# IA_Asserv_Shield.net
KiCad netlist of a schematic drawn in EAGLE
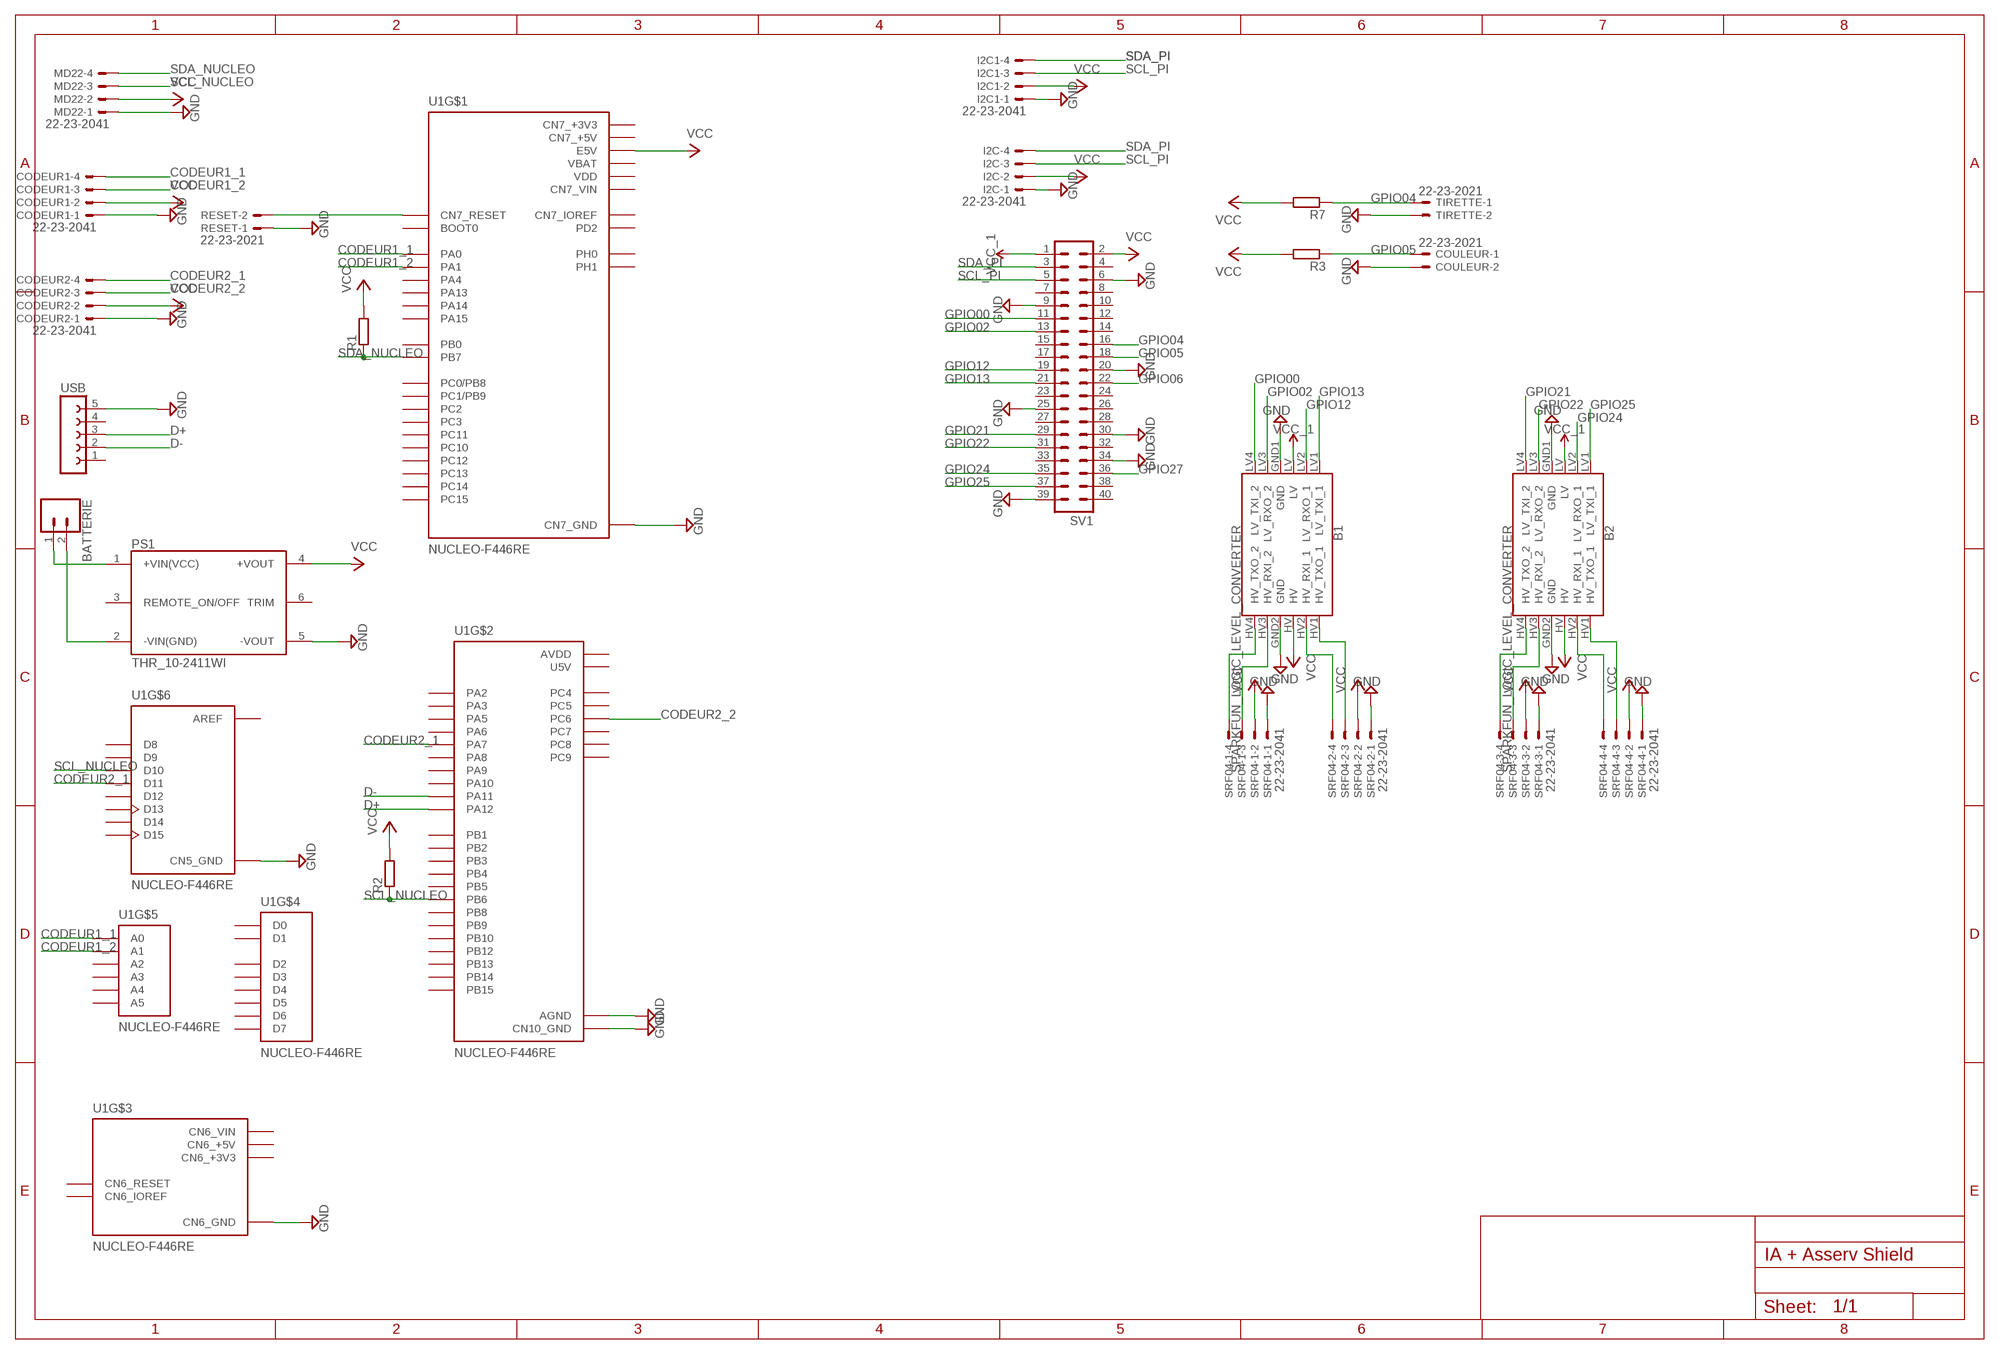
[diagram p0: schematic, sheet 1]

(export (version "E")
  (design (tool "Eeschema 10.0.6"))
  (components
    (comp (ref "B1")
      (value "SPARKFUN_LOGIC_LEVEL_CONVERTER")
      (footprint "eagle-import:SPARKFUN_LOGIC_LEVEL_CONVERTER")
      (libsource (lib "eagle-import") (part "SPARKFUN_LOGIC_LEVEL_CONVERTER"))
    )
    (comp (ref "B2")
      (value "SPARKFUN_LOGIC_LEVEL_CONVERTER")
      (footprint "eagle-import:SPARKFUN_LOGIC_LEVEL_CONVERTER")
      (libsource (lib "eagle-import") (part "SPARKFUN_LOGIC_LEVEL_CONVERTER"))
    )
    (comp (ref "BATTERIE")
      (value "CONN_02POLAR")
      (footprint "eagle-import:MOLEX-1X2")
      (libsource (lib "eagle-import") (part "CONN_02POLAR"))
    )
    (comp (ref "CODEUR1")
      (value "22-23-2041")
      (footprint "eagle-import:22-23-2041")
      (fields (field (name "MF") "MOLEX"))
      (libsource (lib "eagle-import") (part "22-23-2041"))
    )
    (comp (ref "CODEUR2")
      (value "22-23-2041")
      (footprint "eagle-import:22-23-2041")
      (fields (field (name "MF") "MOLEX"))
      (libsource (lib "eagle-import") (part "22-23-2041"))
    )
    (comp (ref "COULEUR")
      (value "22-23-2021")
      (footprint "eagle-import:22-23-2021")
      (fields (field (name "MF") "MOLEX"))
      (libsource (lib "eagle-import") (part "22-23-2021"))
    )
    (comp (ref "I2C")
      (value "22-23-2041")
      (footprint "eagle-import:22-23-2041")
      (fields (field (name "MF") "MOLEX"))
      (libsource (lib "eagle-import") (part "22-23-2041"))
    )
    (comp (ref "I2C1")
      (value "22-23-2041")
      (footprint "eagle-import:22-23-2041")
      (fields (field (name "MF") "MOLEX"))
      (libsource (lib "eagle-import") (part "22-23-2041"))
    )
    (comp (ref "MD22")
      (value "22-23-2041")
      (footprint "eagle-import:22-23-2041")
      (fields (field (name "MF") "MOLEX"))
      (libsource (lib "eagle-import") (part "22-23-2041"))
    )
    (comp (ref "PS1")
      (value "THR_10-2411WI")
      (footprint "eagle-import:CONV_THR_10-2411WI")
      (fields (field (name "MF") "Traco Power") (field (name "MP") "THR 10-2411WI"))
      (libsource (lib "eagle-import") (part "THR_10-2411WI"))
    )
    (comp (ref "R1")
      (value "R-EU_0204/7")
      (footprint "eagle-import:0204_7")
      (libsource (lib "eagle-import") (part "R-EU_0204/7"))
    )
    (comp (ref "R2")
      (value "R-EU_0204/7")
      (footprint "eagle-import:0204_7")
      (libsource (lib "eagle-import") (part "R-EU_0204/7"))
    )
    (comp (ref "R3")
      (value "R-EU_0204/7")
      (footprint "eagle-import:0204_7")
      (libsource (lib "eagle-import") (part "R-EU_0204/7"))
    )
    (comp (ref "R7")
      (value "R-EU_0204/7")
      (footprint "eagle-import:0204_7")
      (libsource (lib "eagle-import") (part "R-EU_0204/7"))
    )
    (comp (ref "RESET")
      (value "22-23-2021")
      (footprint "eagle-import:22-23-2021")
      (fields (field (name "MF") "MOLEX"))
      (libsource (lib "eagle-import") (part "22-23-2021"))
    )
    (comp (ref "SRF04-1")
      (value "22-23-2041")
      (footprint "eagle-import:22-23-2041")
      (fields (field (name "MF") "MOLEX"))
      (libsource (lib "eagle-import") (part "22-23-2041"))
    )
    (comp (ref "SRF04-2")
      (value "22-23-2041")
      (footprint "eagle-import:22-23-2041")
      (fields (field (name "MF") "MOLEX"))
      (libsource (lib "eagle-import") (part "22-23-2041"))
    )
    (comp (ref "SRF04-3")
      (value "22-23-2041")
      (footprint "eagle-import:22-23-2041")
      (fields (field (name "MF") "MOLEX"))
      (libsource (lib "eagle-import") (part "22-23-2041"))
    )
    (comp (ref "SRF04-4")
      (value "22-23-2041")
      (footprint "eagle-import:22-23-2041")
      (fields (field (name "MF") "MOLEX"))
      (libsource (lib "eagle-import") (part "22-23-2041"))
    )
    (comp (ref "SV1")
      (value "MA20-2")
      (footprint "eagle-import:MA20-2")
      (libsource (lib "eagle-import") (part "MA20-2"))
    )
    (comp (ref "TIRETTE")
      (value "22-23-2021")
      (footprint "eagle-import:22-23-2021")
      (fields (field (name "MF") "MOLEX"))
      (libsource (lib "eagle-import") (part "22-23-2021"))
    )
    (comp (ref "U1")
      (value "NUCLEO-F446RE")
      (footprint "eagle-import:MODULE_NUCLEO-F446RE")
      (fields
        (field (name "MF") "STMicroelectronics")
        (field (name "MF_1") "STMICROELECTRONICS")
        (field (name "SPICEPREFIX") "X")
        (field (name "MPN") "NUCLEO-F446RE")
        (field (name "OC_FARNELL") "2491978")
      )
      (libsource (lib "eagle-import") (part "NUCLEO-F446RE"))
    )
    (comp (ref "USB")
      (value "FE05-1")
      (footprint "eagle-import:FE05-1")
      (libsource (lib "eagle-import") (part "FE05-1"))
    )
  )
  (nets
    (net (code "1") (name "/AREF") (class "Default")
      (node (ref "U1") (pin "CN5_8") (pinfunction "AREF_CN5_8") (pintype "power_in"))
    )
    (net (code "2") (name "/AVDD") (class "Default")
      (node (ref "U1") (pin "CN10_7") (pinfunction "AVDD_CN10_7") (pintype "power_in"))
    )
    (net (code "3") (name "/CN6_+3V3") (class "Default")
      (node (ref "U1") (pin "CN6_4") (pinfunction "CN6_+3V3_CN6_4") (pintype "power_in"))
    )
    (net (code "4") (name "/CN6_+5V") (class "Default")
      (node (ref "U1") (pin "CN6_5") (pinfunction "CN6_+5V_CN6_5") (pintype "power_in"))
    )
    (net (code "5") (name "/CN6_VIN") (class "Default")
      (node (ref "U1") (pin "CN6_8") (pinfunction "CN6_VIN_CN6_8") (pintype "power_in"))
    )
    (net (code "6") (name "/CN7_+3V3") (class "Default")
      (node (ref "U1") (pin "CN7_16") (pinfunction "CN7_+3V3_CN7_16") (pintype "power_in"))
    )
    (net (code "7") (name "/CN7_+5V") (class "Default")
      (node (ref "U1") (pin "CN7_18") (pinfunction "CN7_+5V_CN7_18") (pintype "power_in"))
    )
    (net (code "8") (name "/CN7_VIN") (class "Default")
      (node (ref "U1") (pin "CN7_24") (pinfunction "CN7_VIN_CN7_24") (pintype "power_in"))
    )
    (net (code "9") (name "/CODEUR1_1") (class "Default")
      (node (ref "CODEUR1") (pin "4") (pinfunction "S_4") (pintype "passive"))
      (node (ref "U1") (pin "CN7_28") (pinfunction "PA0_CN7_28") (pintype "bidirectional"))
      (node (ref "U1") (pin "CN8_1") (pinfunction "A0_CN8_1") (pintype "input"))
    )
    (net (code "10") (name "/CODEUR1_2") (class "Default")
      (node (ref "CODEUR1") (pin "3") (pinfunction "S_3") (pintype "passive"))
      (node (ref "U1") (pin "CN7_30") (pinfunction "PA1_CN7_30") (pintype "bidirectional"))
      (node (ref "U1") (pin "CN8_2") (pinfunction "A1_CN8_2") (pintype "input"))
    )
    (net (code "11") (name "/CODEUR2_1") (class "Default")
      (node (ref "CODEUR2") (pin "4") (pinfunction "S_4") (pintype "passive"))
      (node (ref "U1") (pin "CN10_15") (pinfunction "PA7_CN10_15") (pintype "bidirectional"))
      (node (ref "U1") (pin "CN5_4") (pinfunction "D11_CN5_4") (pintype "bidirectional"))
    )
    (net (code "12") (name "/CODEUR2_2") (class "Default")
      (node (ref "CODEUR2") (pin "3") (pinfunction "S_3") (pintype "passive"))
      (node (ref "U1") (pin "CN10_4") (pinfunction "PC6_CN10_4") (pintype "bidirectional"))
    )
    (net (code "13") (name "/D+") (class "Default")
      (node (ref "U1") (pin "CN10_12") (pinfunction "PA12_CN10_12") (pintype "bidirectional"))
      (node (ref "USB") (pin "3") (pinfunction "3_3") (pintype "passive"))
    )
    (net (code "14") (name "/D-") (class "Default")
      (node (ref "U1") (pin "CN10_14") (pinfunction "PA11_CN10_14") (pintype "bidirectional"))
      (node (ref "USB") (pin "2") (pinfunction "2_2") (pintype "passive"))
    )
    (net (code "15") (name "/GPIO00") (class "Default")
      (node (ref "B1") (pin "LV4") (pinfunction "LV_TXI_2_LV4") (pintype "bidirectional"))
      (node (ref "SV1") (pin "11") (pinfunction "11_11") (pintype "passive"))
    )
    (net (code "16") (name "/GPIO02") (class "Default")
      (node (ref "B1") (pin "LV3") (pinfunction "LV_RXO_2_LV3") (pintype "bidirectional"))
      (node (ref "SV1") (pin "13") (pinfunction "13_13") (pintype "passive"))
    )
    (net (code "17") (name "/GPIO04") (class "Default")
      (node (ref "R7") (pin "1") (pinfunction "1_1") (pintype "passive"))
      (node (ref "SV1") (pin "16") (pinfunction "16_16") (pintype "passive"))
      (node (ref "TIRETTE") (pin "1") (pinfunction "S_1") (pintype "passive"))
    )
    (net (code "18") (name "/GPIO05") (class "Default")
      (node (ref "COULEUR") (pin "1") (pinfunction "S_1") (pintype "passive"))
      (node (ref "R3") (pin "1") (pinfunction "1_1") (pintype "passive"))
      (node (ref "SV1") (pin "18") (pinfunction "18_18") (pintype "passive"))
    )
    (net (code "19") (name "/GPIO06") (class "Default")
      (node (ref "SV1") (pin "22") (pinfunction "22_22") (pintype "passive"))
    )
    (net (code "20") (name "/GPIO12") (class "Default")
      (node (ref "B1") (pin "LV2") (pinfunction "LV_RXO_1_LV2") (pintype "bidirectional"))
      (node (ref "SV1") (pin "19") (pinfunction "19_19") (pintype "passive"))
    )
    (net (code "21") (name "/GPIO13") (class "Default")
      (node (ref "B1") (pin "LV1") (pinfunction "LV_TXI_1_LV1") (pintype "bidirectional"))
      (node (ref "SV1") (pin "21") (pinfunction "21_21") (pintype "passive"))
    )
    (net (code "22") (name "/GPIO21") (class "Default")
      (node (ref "B2") (pin "LV4") (pinfunction "LV_TXI_2_LV4") (pintype "bidirectional"))
      (node (ref "SV1") (pin "29") (pinfunction "29_29") (pintype "passive"))
    )
    (net (code "23") (name "/GPIO22") (class "Default")
      (node (ref "B2") (pin "LV3") (pinfunction "LV_RXO_2_LV3") (pintype "bidirectional"))
      (node (ref "SV1") (pin "31") (pinfunction "31_31") (pintype "passive"))
    )
    (net (code "24") (name "/GPIO24") (class "Default")
      (node (ref "B2") (pin "LV2") (pinfunction "LV_RXO_1_LV2") (pintype "bidirectional"))
      (node (ref "SV1") (pin "35") (pinfunction "35_35") (pintype "passive"))
    )
    (net (code "25") (name "/GPIO25") (class "Default")
      (node (ref "B2") (pin "LV1") (pinfunction "LV_TXI_1_LV1") (pintype "bidirectional"))
      (node (ref "SV1") (pin "37") (pinfunction "37_37") (pintype "passive"))
    )
    (net (code "26") (name "/GPIO27") (class "Default")
      (node (ref "SV1") (pin "36") (pinfunction "36_36") (pintype "passive"))
    )
    (net (code "27") (name "/SCL_NUCLEO") (class "Default")
      (node (ref "MD22") (pin "3") (pinfunction "S_3") (pintype "passive"))
      (node (ref "R2") (pin "1") (pinfunction "1_1") (pintype "passive"))
      (node (ref "U1") (pin "CN10_17") (pinfunction "PB6_CN10_17") (pintype "bidirectional"))
      (node (ref "U1") (pin "CN5_3") (pinfunction "D10_CN5_3") (pintype "bidirectional"))
    )
    (net (code "28") (name "/SCL_PI") (class "Default")
      (node (ref "I2C") (pin "3") (pinfunction "S_3") (pintype "passive"))
      (node (ref "I2C1") (pin "3") (pinfunction "S_3") (pintype "passive"))
      (node (ref "SV1") (pin "5") (pinfunction "5_5") (pintype "passive"))
    )
    (net (code "29") (name "/SDA_NUCLEO") (class "Default")
      (node (ref "MD22") (pin "4") (pinfunction "S_4") (pintype "passive"))
      (node (ref "R1") (pin "1") (pinfunction "1_1") (pintype "passive"))
      (node (ref "U1") (pin "CN7_21") (pinfunction "PB7_CN7_21") (pintype "bidirectional"))
    )
    (net (code "30") (name "/SDA_PI") (class "Default")
      (node (ref "I2C") (pin "4") (pinfunction "S_4") (pintype "passive"))
      (node (ref "I2C1") (pin "4") (pinfunction "S_4") (pintype "passive"))
      (node (ref "SV1") (pin "3") (pinfunction "3_3") (pintype "passive"))
    )
    (net (code "31") (name "/U5V") (class "Default")
      (node (ref "U1") (pin "CN10_8") (pinfunction "U5V_CN10_8") (pintype "power_in"))
    )
    (net (code "32") (name "/VBAT") (class "Default")
      (node (ref "U1") (pin "CN7_33") (pinfunction "VBAT_CN7_33") (pintype "power_in"))
    )
    (net (code "33") (name "/VDD") (class "Default")
      (node (ref "U1") (pin "CN7_5") (pinfunction "VDD_CN7_5") (pintype "power_in"))
    )
    (net (code "34") (name "GND") (class "Default")
      (node (ref "B1") (pin "GND1") (pinfunction "GND_GND1") (pintype "power_in"))
      (node (ref "B1") (pin "GND2") (pinfunction "GND_GND2") (pintype "power_in"))
      (node (ref "B2") (pin "GND1") (pinfunction "GND_GND1") (pintype "power_in"))
      (node (ref "B2") (pin "GND2") (pinfunction "GND_GND2") (pintype "power_in"))
      (node (ref "CODEUR1") (pin "1") (pinfunction "S_1") (pintype "passive"))
      (node (ref "CODEUR2") (pin "1") (pinfunction "S_1") (pintype "passive"))
      (node (ref "COULEUR") (pin "2") (pinfunction "S_2") (pintype "passive"))
      (node (ref "I2C") (pin "1") (pinfunction "S_1") (pintype "passive"))
      (node (ref "I2C1") (pin "1") (pinfunction "S_1") (pintype "passive"))
      (node (ref "MD22") (pin "1") (pinfunction "S_1") (pintype "passive"))
      (node (ref "PS1") (pin "5") (pinfunction "-VOUT_5") (pintype "output"))
      (node (ref "RESET") (pin "1") (pinfunction "S_1") (pintype "passive"))
      (node (ref "SRF04-1") (pin "1") (pinfunction "S_1") (pintype "passive"))
      (node (ref "SRF04-2") (pin "1") (pinfunction "S_1") (pintype "passive"))
      (node (ref "SRF04-3") (pin "1") (pinfunction "S_1") (pintype "passive"))
      (node (ref "SRF04-4") (pin "1") (pinfunction "S_1") (pintype "passive"))
      (node (ref "SV1") (pin "20") (pinfunction "20_20") (pintype "passive"))
      (node (ref "SV1") (pin "25") (pinfunction "25_25") (pintype "passive"))
      (node (ref "SV1") (pin "30") (pinfunction "30_30") (pintype "passive"))
      (node (ref "SV1") (pin "34") (pinfunction "34_34") (pintype "passive"))
      (node (ref "SV1") (pin "39") (pinfunction "39_39") (pintype "passive"))
      (node (ref "SV1") (pin "6") (pinfunction "6_6") (pintype "passive"))
      (node (ref "SV1") (pin "9") (pinfunction "9_9") (pintype "passive"))
      (node (ref "TIRETTE") (pin "2") (pinfunction "S_2") (pintype "passive"))
      (node (ref "U1") (pin "CN10_20") (pinfunction "CN10_GND_CN10_20") (pintype "power_in"))
      (node (ref "U1") (pin "CN10_32") (pinfunction "AGND_CN10_32") (pintype "power_in"))
      (node (ref "U1") (pin "CN10_9") (pinfunction "CN10_GND_CN10_9") (pintype "power_in"))
      (node (ref "U1") (pin "CN5_7") (pinfunction "CN5_GND_CN5_7") (pintype "power_in"))
      (node (ref "U1") (pin "CN6_6") (pinfunction "CN6_GND_CN6_6") (pintype "power_in"))
      (node (ref "U1") (pin "CN6_7") (pinfunction "CN6_GND_CN6_7") (pintype "power_in"))
      (node (ref "U1") (pin "CN7_19") (pinfunction "CN7_GND_CN7_19") (pintype "power_in"))
      (node (ref "U1") (pin "CN7_20") (pinfunction "CN7_GND_CN7_20") (pintype "power_in"))
      (node (ref "U1") (pin "CN7_22") (pinfunction "CN7_GND_CN7_22") (pintype "power_in"))
      (node (ref "U1") (pin "CN7_8") (pinfunction "CN7_GND_CN7_8") (pintype "power_in"))
      (node (ref "USB") (pin "5") (pinfunction "5_5") (pintype "passive"))
    )
    (net (code "35") (name "Net-(B1-HV_RXI_1)") (class "Default")
      (node (ref "B1") (pin "HV2") (pinfunction "HV_RXI_1_HV2") (pintype "bidirectional"))
      (node (ref "SRF04-2") (pin "4") (pinfunction "S_4") (pintype "passive"))
    )
    (net (code "36") (name "Net-(B1-HV_RXI_2)") (class "Default")
      (node (ref "B1") (pin "HV3") (pinfunction "HV_RXI_2_HV3") (pintype "bidirectional"))
      (node (ref "SRF04-1") (pin "3") (pinfunction "S_3") (pintype "passive"))
    )
    (net (code "37") (name "Net-(B1-HV_TXO_1)") (class "Default")
      (node (ref "B1") (pin "HV1") (pinfunction "HV_TXO_1_HV1") (pintype "bidirectional"))
      (node (ref "SRF04-2") (pin "3") (pinfunction "S_3") (pintype "passive"))
    )
    (net (code "38") (name "Net-(B1-HV_TXO_2)") (class "Default")
      (node (ref "B1") (pin "HV4") (pinfunction "HV_TXO_2_HV4") (pintype "bidirectional"))
      (node (ref "SRF04-1") (pin "4") (pinfunction "S_4") (pintype "passive"))
    )
    (net (code "39") (name "Net-(B2-HV_RXI_1)") (class "Default")
      (node (ref "B2") (pin "HV2") (pinfunction "HV_RXI_1_HV2") (pintype "bidirectional"))
      (node (ref "SRF04-4") (pin "4") (pinfunction "S_4") (pintype "passive"))
    )
    (net (code "40") (name "Net-(B2-HV_RXI_2)") (class "Default")
      (node (ref "B2") (pin "HV3") (pinfunction "HV_RXI_2_HV3") (pintype "bidirectional"))
      (node (ref "SRF04-3") (pin "3") (pinfunction "S_3") (pintype "passive"))
    )
    (net (code "41") (name "Net-(B2-HV_TXO_1)") (class "Default")
      (node (ref "B2") (pin "HV1") (pinfunction "HV_TXO_1_HV1") (pintype "bidirectional"))
      (node (ref "SRF04-4") (pin "3") (pinfunction "S_3") (pintype "passive"))
    )
    (net (code "42") (name "Net-(B2-HV_TXO_2)") (class "Default")
      (node (ref "B2") (pin "HV4") (pinfunction "HV_TXO_2_HV4") (pintype "bidirectional"))
      (node (ref "SRF04-3") (pin "4") (pinfunction "S_4") (pintype "passive"))
    )
    (net (code "43") (name "Net-(PS1-+VIN(VCC))") (class "Default")
      (node (ref "BATTERIE") (pin "1") (pinfunction "1_1") (pintype "passive"))
      (node (ref "PS1") (pin "1") (pinfunction "+VIN(VCC)_1") (pintype "input"))
    )
    (net (code "44") (name "Net-(PS1--VIN(GND))") (class "Default")
      (node (ref "BATTERIE") (pin "2") (pinfunction "2_2") (pintype "passive"))
      (node (ref "PS1") (pin "2") (pinfunction "-VIN(GND)_2") (pintype "input"))
    )
    (net (code "45") (name "Net-(RESETB-S)") (class "Default")
      (node (ref "RESET") (pin "2") (pinfunction "S_2") (pintype "passive"))
      (node (ref "U1") (pin "CN7_14") (pinfunction "CN7_RESET_CN7_14") (pintype "bidirectional"))
    )
    (net (code "46") (name "VCC") (class "Default")
      (node (ref "B1") (pin "HV") (pinfunction "HV_HV") (pintype "power_in"))
      (node (ref "B2") (pin "HV") (pinfunction "HV_HV") (pintype "power_in"))
      (node (ref "CODEUR1") (pin "2") (pinfunction "S_2") (pintype "passive"))
      (node (ref "CODEUR2") (pin "2") (pinfunction "S_2") (pintype "passive"))
      (node (ref "I2C") (pin "2") (pinfunction "S_2") (pintype "passive"))
      (node (ref "I2C1") (pin "2") (pinfunction "S_2") (pintype "passive"))
      (node (ref "MD22") (pin "2") (pinfunction "S_2") (pintype "passive"))
      (node (ref "PS1") (pin "4") (pinfunction "+VOUT_4") (pintype "output"))
      (node (ref "R1") (pin "2") (pinfunction "2_2") (pintype "passive"))
      (node (ref "R2") (pin "2") (pinfunction "2_2") (pintype "passive"))
      (node (ref "R3") (pin "2") (pinfunction "2_2") (pintype "passive"))
      (node (ref "R7") (pin "2") (pinfunction "2_2") (pintype "passive"))
      (node (ref "SRF04-1") (pin "2") (pinfunction "S_2") (pintype "passive"))
      (node (ref "SRF04-2") (pin "2") (pinfunction "S_2") (pintype "passive"))
      (node (ref "SRF04-3") (pin "2") (pinfunction "S_2") (pintype "passive"))
      (node (ref "SRF04-4") (pin "2") (pinfunction "S_2") (pintype "passive"))
      (node (ref "SV1") (pin "2") (pinfunction "2_2") (pintype "passive"))
      (node (ref "U1") (pin "CN7_6") (pinfunction "E5V_CN7_6") (pintype "power_in"))
    )
    (net (code "47") (name "VCC_1") (class "Default")
      (node (ref "B1") (pin "LV") (pinfunction "LV_LV") (pintype "power_in"))
      (node (ref "B2") (pin "LV") (pinfunction "LV_LV") (pintype "power_in"))
      (node (ref "SV1") (pin "1") (pinfunction "1_1") (pintype "passive"))
    )
    (net (code "48") (name "unconnected-(PS1-REMOTE_ON{slash}OFF-Pad3)") (class "Default")
      (node (ref "PS1") (pin "3") (pinfunction "REMOTE_ON/OFF_3") (pintype "input"))
    )
    (net (code "49") (name "unconnected-(PS1-TRIM-Pad6)") (class "Default")
      (node (ref "PS1") (pin "6") (pinfunction "TRIM_6") (pintype "passive"))
    )
    (net (code "50") (name "unconnected-(SV1-Pad4)") (class "Default")
      (node (ref "SV1") (pin "4") (pinfunction "4_4") (pintype "passive"))
    )
    (net (code "51") (name "unconnected-(SV1-Pad7)") (class "Default")
      (node (ref "SV1") (pin "7") (pinfunction "7_7") (pintype "passive"))
    )
    (net (code "52") (name "unconnected-(SV1-Pad8)") (class "Default")
      (node (ref "SV1") (pin "8") (pinfunction "8_8") (pintype "passive"))
    )
    (net (code "53") (name "unconnected-(SV1-Pad10)") (class "Default")
      (node (ref "SV1") (pin "10") (pinfunction "10_10") (pintype "passive"))
    )
    (net (code "54") (name "unconnected-(SV1-Pad12)") (class "Default")
      (node (ref "SV1") (pin "12") (pinfunction "12_12") (pintype "passive"))
    )
    (net (code "55") (name "unconnected-(SV1-Pad14)") (class "Default")
      (node (ref "SV1") (pin "14") (pinfunction "14_14") (pintype "passive"))
    )
    (net (code "56") (name "unconnected-(SV1-Pad15)") (class "Default")
      (node (ref "SV1") (pin "15") (pinfunction "15_15") (pintype "passive"))
    )
    (net (code "57") (name "unconnected-(SV1-Pad17)") (class "Default")
      (node (ref "SV1") (pin "17") (pinfunction "17_17") (pintype "passive"))
    )
    (net (code "58") (name "unconnected-(SV1-Pad23)") (class "Default")
      (node (ref "SV1") (pin "23") (pinfunction "23_23") (pintype "passive"))
    )
    (net (code "59") (name "unconnected-(SV1-Pad24)") (class "Default")
      (node (ref "SV1") (pin "24") (pinfunction "24_24") (pintype "passive"))
    )
    (net (code "60") (name "unconnected-(SV1-Pad26)") (class "Default")
      (node (ref "SV1") (pin "26") (pinfunction "26_26") (pintype "passive"))
    )
    (net (code "61") (name "unconnected-(SV1-Pad27)") (class "Default")
      (node (ref "SV1") (pin "27") (pinfunction "27_27") (pintype "passive"))
    )
    (net (code "62") (name "unconnected-(SV1-Pad28)") (class "Default")
      (node (ref "SV1") (pin "28") (pinfunction "28_28") (pintype "passive"))
    )
    (net (code "63") (name "unconnected-(SV1-Pad32)") (class "Default")
      (node (ref "SV1") (pin "32") (pinfunction "32_32") (pintype "passive"))
    )
    (net (code "64") (name "unconnected-(SV1-Pad33)") (class "Default")
      (node (ref "SV1") (pin "33") (pinfunction "33_33") (pintype "passive"))
    )
    (net (code "65") (name "unconnected-(SV1-Pad38)") (class "Default")
      (node (ref "SV1") (pin "38") (pinfunction "38_38") (pintype "passive"))
    )
    (net (code "66") (name "unconnected-(SV1-Pad40)") (class "Default")
      (node (ref "SV1") (pin "40") (pinfunction "40_40") (pintype "passive"))
    )
    (net (code "67") (name "unconnected-(U1A-BOOT0-PadCN7_7)") (class "Default")
      (node (ref "U1") (pin "CN7_7") (pinfunction "BOOT0_CN7_7") (pintype "bidirectional"))
    )
    (net (code "68") (name "unconnected-(U1A-CN7_IOREF-PadCN7_12)") (class "Default")
      (node (ref "U1") (pin "CN7_12") (pinfunction "CN7_IOREF_CN7_12") (pintype "bidirectional"))
    )
    (net (code "69") (name "unconnected-(U1A-PA4-PadCN7_32)") (class "Default")
      (node (ref "U1") (pin "CN7_32") (pinfunction "PA4_CN7_32") (pintype "bidirectional"))
    )
    (net (code "70") (name "unconnected-(U1A-PA13-PadCN7_13)") (class "Default")
      (node (ref "U1") (pin "CN7_13") (pinfunction "PA13_CN7_13") (pintype "bidirectional"))
    )
    (net (code "71") (name "unconnected-(U1A-PA14-PadCN7_15)") (class "Default")
      (node (ref "U1") (pin "CN7_15") (pinfunction "PA14_CN7_15") (pintype "bidirectional"))
    )
    (net (code "72") (name "unconnected-(U1A-PA15-PadCN7_17)") (class "Default")
      (node (ref "U1") (pin "CN7_17") (pinfunction "PA15_CN7_17") (pintype "bidirectional"))
    )
    (net (code "73") (name "unconnected-(U1A-PB0-PadCN7_34)") (class "Default")
      (node (ref "U1") (pin "CN7_34") (pinfunction "PB0_CN7_34") (pintype "bidirectional"))
    )
    (net (code "74") (name "unconnected-(U1A-PC0{slash}PB8-PadCN7_38)") (class "Default")
      (node (ref "U1") (pin "CN7_38") (pinfunction "PC0/PB8_CN7_38") (pintype "bidirectional"))
    )
    (net (code "75") (name "unconnected-(U1A-PC1{slash}PB9-PadCN7_36)") (class "Default")
      (node (ref "U1") (pin "CN7_36") (pinfunction "PC1/PB9_CN7_36") (pintype "bidirectional"))
    )
    (net (code "76") (name "unconnected-(U1A-PC2-PadCN7_35)") (class "Default")
      (node (ref "U1") (pin "CN7_35") (pinfunction "PC2_CN7_35") (pintype "bidirectional"))
    )
    (net (code "77") (name "unconnected-(U1A-PC3-PadCN7_37)") (class "Default")
      (node (ref "U1") (pin "CN7_37") (pinfunction "PC3_CN7_37") (pintype "bidirectional"))
    )
    (net (code "78") (name "unconnected-(U1A-PC10-PadCN7_1)") (class "Default")
      (node (ref "U1") (pin "CN7_1") (pinfunction "PC10_CN7_1") (pintype "bidirectional"))
    )
    (net (code "79") (name "unconnected-(U1A-PC11-PadCN7_2)") (class "Default")
      (node (ref "U1") (pin "CN7_2") (pinfunction "PC11_CN7_2") (pintype "bidirectional"))
    )
    (net (code "80") (name "unconnected-(U1A-PC12-PadCN7_3)") (class "Default")
      (node (ref "U1") (pin "CN7_3") (pinfunction "PC12_CN7_3") (pintype "bidirectional"))
    )
    (net (code "81") (name "unconnected-(U1A-PC13-PadCN7_23)") (class "Default")
      (node (ref "U1") (pin "CN7_23") (pinfunction "PC13_CN7_23") (pintype "bidirectional"))
    )
    (net (code "82") (name "unconnected-(U1A-PC14-PadCN7_25)") (class "Default")
      (node (ref "U1") (pin "CN7_25") (pinfunction "PC14_CN7_25") (pintype "bidirectional"))
    )
    (net (code "83") (name "unconnected-(U1A-PC15-PadCN7_27)") (class "Default")
      (node (ref "U1") (pin "CN7_27") (pinfunction "PC15_CN7_27") (pintype "bidirectional"))
    )
    (net (code "84") (name "unconnected-(U1A-PD2-PadCN7_4)") (class "Default")
      (node (ref "U1") (pin "CN7_4") (pinfunction "PD2_CN7_4") (pintype "bidirectional"))
    )
    (net (code "85") (name "unconnected-(U1A-PH0-PadCN7_29)") (class "Default")
      (node (ref "U1") (pin "CN7_29") (pinfunction "PH0_CN7_29") (pintype "bidirectional"))
    )
    (net (code "86") (name "unconnected-(U1A-PH1-PadCN7_31)") (class "Default")
      (node (ref "U1") (pin "CN7_31") (pinfunction "PH1_CN7_31") (pintype "bidirectional"))
    )
    (net (code "87") (name "unconnected-(U1B-PA2-PadCN10_35)") (class "Default")
      (node (ref "U1") (pin "CN10_35") (pinfunction "PA2_CN10_35") (pintype "bidirectional"))
    )
    (net (code "88") (name "unconnected-(U1B-PA3-PadCN10_37)") (class "Default")
      (node (ref "U1") (pin "CN10_37") (pinfunction "PA3_CN10_37") (pintype "bidirectional"))
    )
    (net (code "89") (name "unconnected-(U1B-PA5-PadCN10_11)") (class "Default")
      (node (ref "U1") (pin "CN10_11") (pinfunction "PA5_CN10_11") (pintype "bidirectional"))
    )
    (net (code "90") (name "unconnected-(U1B-PA6-PadCN10_13)") (class "Default")
      (node (ref "U1") (pin "CN10_13") (pinfunction "PA6_CN10_13") (pintype "bidirectional"))
    )
    (net (code "91") (name "unconnected-(U1B-PA8-PadCN10_23)") (class "Default")
      (node (ref "U1") (pin "CN10_23") (pinfunction "PA8_CN10_23") (pintype "bidirectional"))
    )
    (net (code "92") (name "unconnected-(U1B-PA9-PadCN10_21)") (class "Default")
      (node (ref "U1") (pin "CN10_21") (pinfunction "PA9_CN10_21") (pintype "bidirectional"))
    )
    (net (code "93") (name "unconnected-(U1B-PA10-PadCN10_33)") (class "Default")
      (node (ref "U1") (pin "CN10_33") (pinfunction "PA10_CN10_33") (pintype "bidirectional"))
    )
    (net (code "94") (name "unconnected-(U1B-PB1-PadCN10_24)") (class "Default")
      (node (ref "U1") (pin "CN10_24") (pinfunction "PB1_CN10_24") (pintype "bidirectional"))
    )
    (net (code "95") (name "unconnected-(U1B-PB2-PadCN10_22)") (class "Default")
      (node (ref "U1") (pin "CN10_22") (pinfunction "PB2_CN10_22") (pintype "bidirectional"))
    )
    (net (code "96") (name "unconnected-(U1B-PB3-PadCN10_31)") (class "Default")
      (node (ref "U1") (pin "CN10_31") (pinfunction "PB3_CN10_31") (pintype "bidirectional"))
    )
    (net (code "97") (name "unconnected-(U1B-PB4-PadCN10_27)") (class "Default")
      (node (ref "U1") (pin "CN10_27") (pinfunction "PB4_CN10_27") (pintype "bidirectional"))
    )
    (net (code "98") (name "unconnected-(U1B-PB5-PadCN10_29)") (class "Default")
      (node (ref "U1") (pin "CN10_29") (pinfunction "PB5_CN10_29") (pintype "bidirectional"))
    )
    (net (code "99") (name "unconnected-(U1B-PB8-PadCN10_3)") (class "Default")
      (node (ref "U1") (pin "CN10_3") (pinfunction "PB8_CN10_3") (pintype "bidirectional"))
    )
    (net (code "100") (name "unconnected-(U1B-PB9-PadCN10_5)") (class "Default")
      (node (ref "U1") (pin "CN10_5") (pinfunction "PB9_CN10_5") (pintype "bidirectional"))
    )
    (net (code "101") (name "unconnected-(U1B-PB10-PadCN10_25)") (class "Default")
      (node (ref "U1") (pin "CN10_25") (pinfunction "PB10_CN10_25") (pintype "bidirectional"))
    )
    (net (code "102") (name "unconnected-(U1B-PB12-PadCN10_16)") (class "Default")
      (node (ref "U1") (pin "CN10_16") (pinfunction "PB12_CN10_16") (pintype "bidirectional"))
    )
    (net (code "103") (name "unconnected-(U1B-PB13-PadCN10_30)") (class "Default")
      (node (ref "U1") (pin "CN10_30") (pinfunction "PB13_CN10_30") (pintype "bidirectional"))
    )
    (net (code "104") (name "unconnected-(U1B-PB14-PadCN10_28)") (class "Default")
      (node (ref "U1") (pin "CN10_28") (pinfunction "PB14_CN10_28") (pintype "bidirectional"))
    )
    (net (code "105") (name "unconnected-(U1B-PB15-PadCN10_26)") (class "Default")
      (node (ref "U1") (pin "CN10_26") (pinfunction "PB15_CN10_26") (pintype "bidirectional"))
    )
    (net (code "106") (name "unconnected-(U1B-PC4-PadCN10_34)") (class "Default")
      (node (ref "U1") (pin "CN10_34") (pinfunction "PC4_CN10_34") (pintype "bidirectional"))
    )
    (net (code "107") (name "unconnected-(U1B-PC5-PadCN10_6)") (class "Default")
      (node (ref "U1") (pin "CN10_6") (pinfunction "PC5_CN10_6") (pintype "bidirectional"))
    )
    (net (code "108") (name "unconnected-(U1B-PC7-PadCN10_19)") (class "Default")
      (node (ref "U1") (pin "CN10_19") (pinfunction "PC7_CN10_19") (pintype "bidirectional"))
    )
    (net (code "109") (name "unconnected-(U1B-PC8-PadCN10_2)") (class "Default")
      (node (ref "U1") (pin "CN10_2") (pinfunction "PC8_CN10_2") (pintype "bidirectional"))
    )
    (net (code "110") (name "unconnected-(U1B-PC9-PadCN10_1)") (class "Default")
      (node (ref "U1") (pin "CN10_1") (pinfunction "PC9_CN10_1") (pintype "bidirectional"))
    )
    (net (code "111") (name "unconnected-(U1C-CN6_IOREF-PadCN6_2)") (class "Default")
      (node (ref "U1") (pin "CN6_2") (pinfunction "CN6_IOREF_CN6_2") (pintype "bidirectional"))
    )
    (net (code "112") (name "unconnected-(U1C-CN6_RESET-PadCN6_3)") (class "Default")
      (node (ref "U1") (pin "CN6_3") (pinfunction "CN6_RESET_CN6_3") (pintype "bidirectional"))
    )
    (net (code "113") (name "unconnected-(U1D-D0-PadCN9_1)") (class "Default")
      (node (ref "U1") (pin "CN9_1") (pinfunction "D0_CN9_1") (pintype "input"))
    )
    (net (code "114") (name "unconnected-(U1D-D1-PadCN9_2)") (class "Default")
      (node (ref "U1") (pin "CN9_2") (pinfunction "D1_CN9_2") (pintype "output"))
    )
    (net (code "115") (name "unconnected-(U1D-D2-PadCN9_3)") (class "Default")
      (node (ref "U1") (pin "CN9_3") (pinfunction "D2_CN9_3") (pintype "bidirectional"))
    )
    (net (code "116") (name "unconnected-(U1D-D3-PadCN9_4)") (class "Default")
      (node (ref "U1") (pin "CN9_4") (pinfunction "D3_CN9_4") (pintype "bidirectional"))
    )
    (net (code "117") (name "unconnected-(U1D-D4-PadCN9_5)") (class "Default")
      (node (ref "U1") (pin "CN9_5") (pinfunction "D4_CN9_5") (pintype "bidirectional"))
    )
    (net (code "118") (name "unconnected-(U1D-D5-PadCN9_6)") (class "Default")
      (node (ref "U1") (pin "CN9_6") (pinfunction "D5_CN9_6") (pintype "bidirectional"))
    )
    (net (code "119") (name "unconnected-(U1D-D6-PadCN9_7)") (class "Default")
      (node (ref "U1") (pin "CN9_7") (pinfunction "D6_CN9_7") (pintype "bidirectional"))
    )
    (net (code "120") (name "unconnected-(U1D-D7-PadCN9_8)") (class "Default")
      (node (ref "U1") (pin "CN9_8") (pinfunction "D7_CN9_8") (pintype "bidirectional"))
    )
    (net (code "121") (name "unconnected-(U1E-A2-PadCN8_3)") (class "Default")
      (node (ref "U1") (pin "CN8_3") (pinfunction "A2_CN8_3") (pintype "input"))
    )
    (net (code "122") (name "unconnected-(U1E-A3-PadCN8_4)") (class "Default")
      (node (ref "U1") (pin "CN8_4") (pinfunction "A3_CN8_4") (pintype "input"))
    )
    (net (code "123") (name "unconnected-(U1E-A4-PadCN8_5)") (class "Default")
      (node (ref "U1") (pin "CN8_5") (pinfunction "A4_CN8_5") (pintype "input"))
    )
    (net (code "124") (name "unconnected-(U1E-A5-PadCN8_6)") (class "Default")
      (node (ref "U1") (pin "CN8_6") (pinfunction "A5_CN8_6") (pintype "input"))
    )
    (net (code "125") (name "unconnected-(U1F-D8-PadCN5_1)") (class "Default")
      (node (ref "U1") (pin "CN5_1") (pinfunction "D8_CN5_1") (pintype "bidirectional"))
    )
    (net (code "126") (name "unconnected-(U1F-D9-PadCN5_2)") (class "Default")
      (node (ref "U1") (pin "CN5_2") (pinfunction "D9_CN5_2") (pintype "bidirectional"))
    )
    (net (code "127") (name "unconnected-(U1F-D12-PadCN5_5)") (class "Default")
      (node (ref "U1") (pin "CN5_5") (pinfunction "D12_CN5_5") (pintype "bidirectional"))
    )
    (net (code "128") (name "unconnected-(U1F-D13-PadCN5_6)") (class "Default")
      (node (ref "U1") (pin "CN5_6") (pinfunction "D13_CN5_6") (pintype "bidirectional"))
    )
    (net (code "129") (name "unconnected-(U1F-D14-PadCN5_9)") (class "Default")
      (node (ref "U1") (pin "CN5_9") (pinfunction "D14_CN5_9") (pintype "bidirectional"))
    )
    (net (code "130") (name "unconnected-(U1F-D15-PadCN5_10)") (class "Default")
      (node (ref "U1") (pin "CN5_10") (pinfunction "D15_CN5_10") (pintype "bidirectional"))
    )
    (net (code "131") (name "unconnected-(USB-Pad1)") (class "Default")
      (node (ref "USB") (pin "1") (pinfunction "1_1") (pintype "passive"))
    )
    (net (code "132") (name "unconnected-(USB-Pad4)") (class "Default")
      (node (ref "USB") (pin "4") (pinfunction "4_4") (pintype "passive"))
    )
  )
)
